# scrump.net
KiCad netlist of a schematic drawn in EAGLE
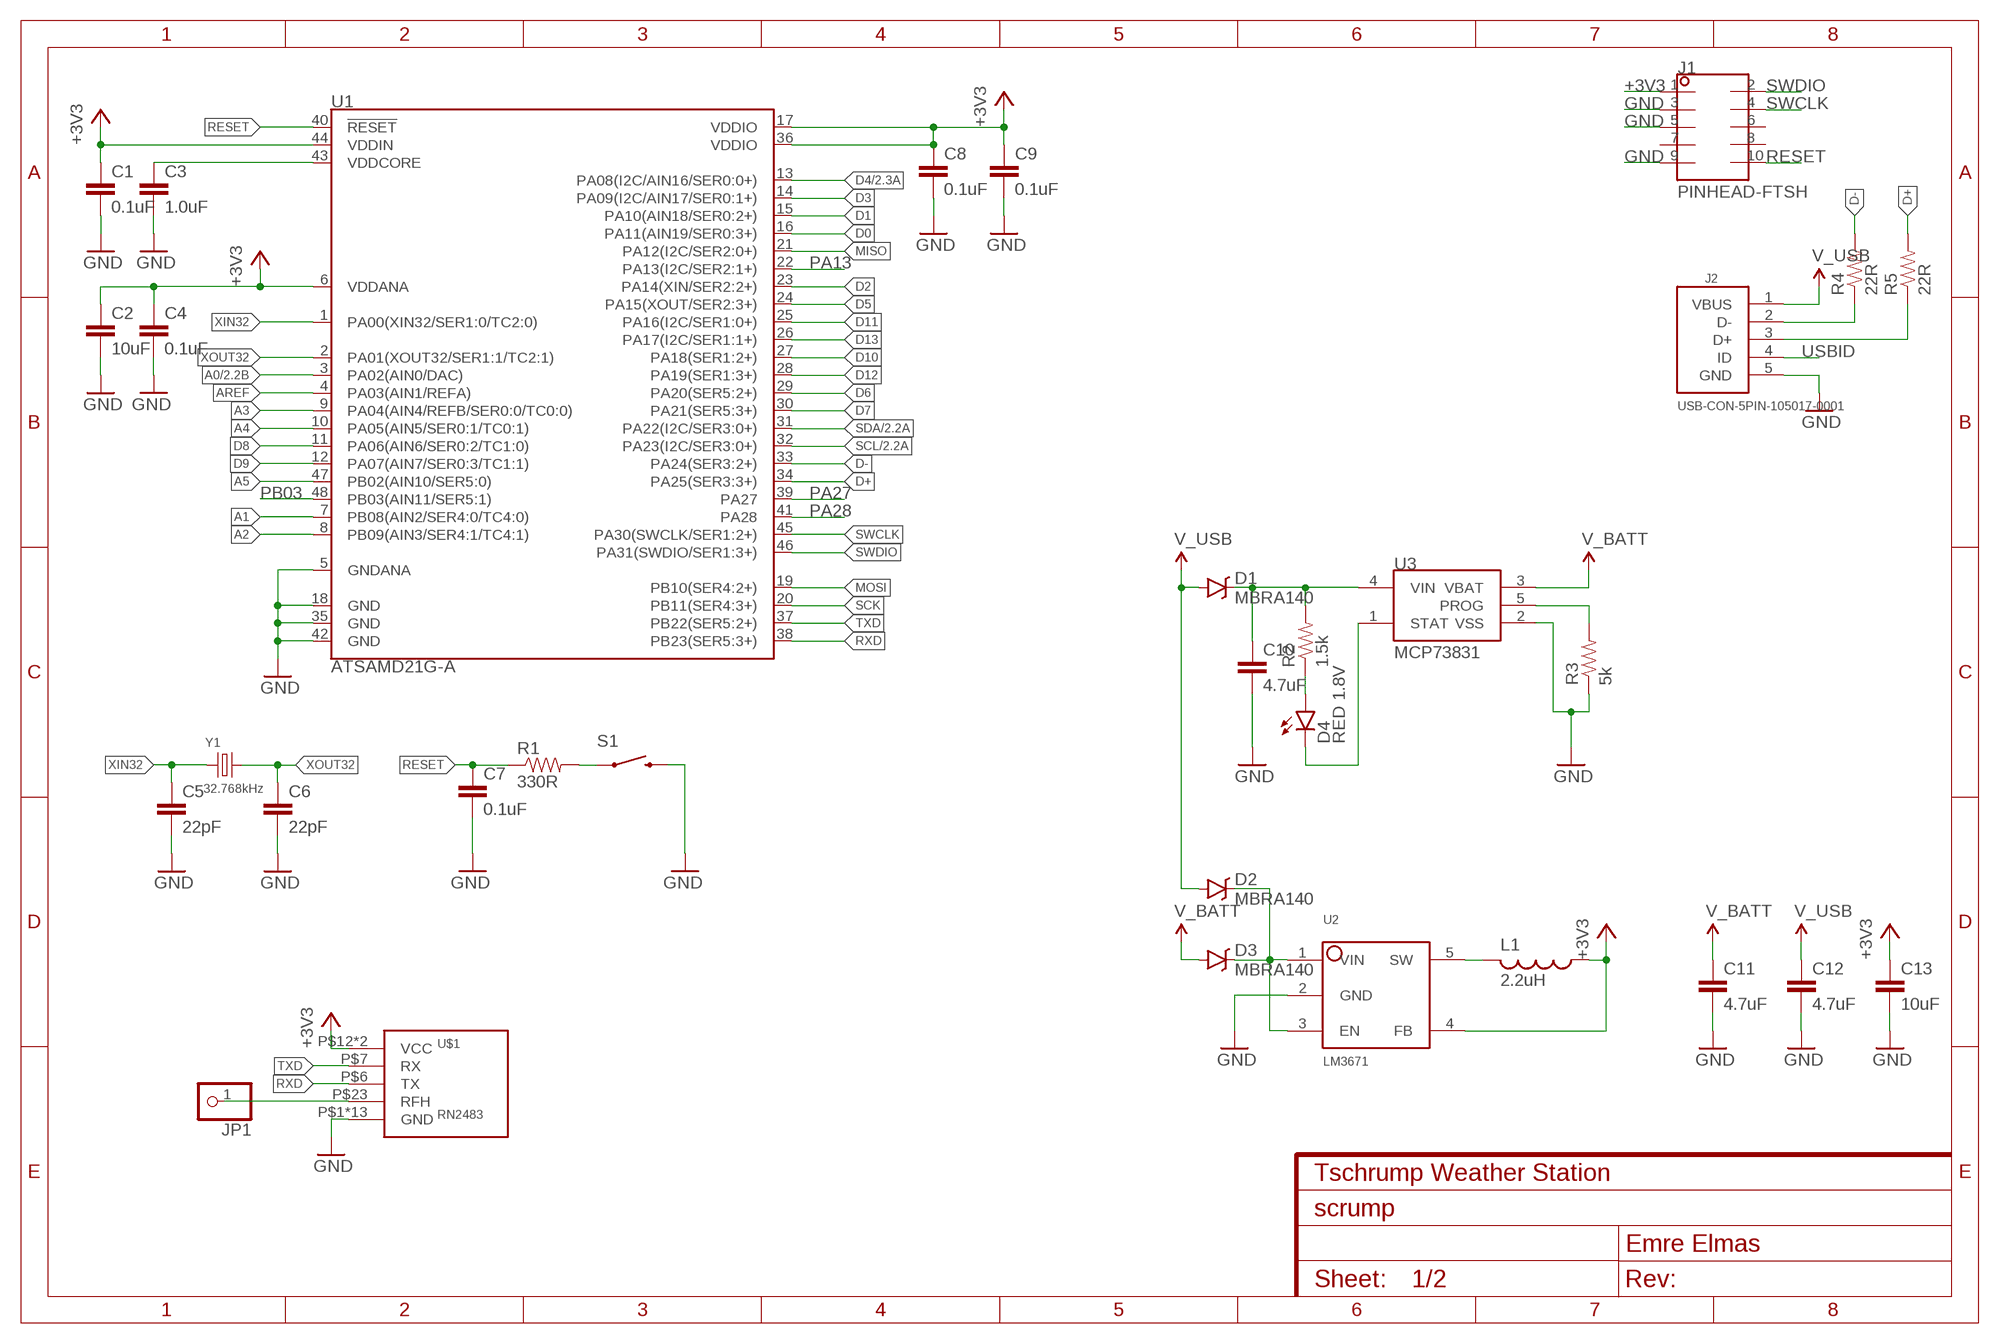
[diagram p0: schematic, sheet 1]
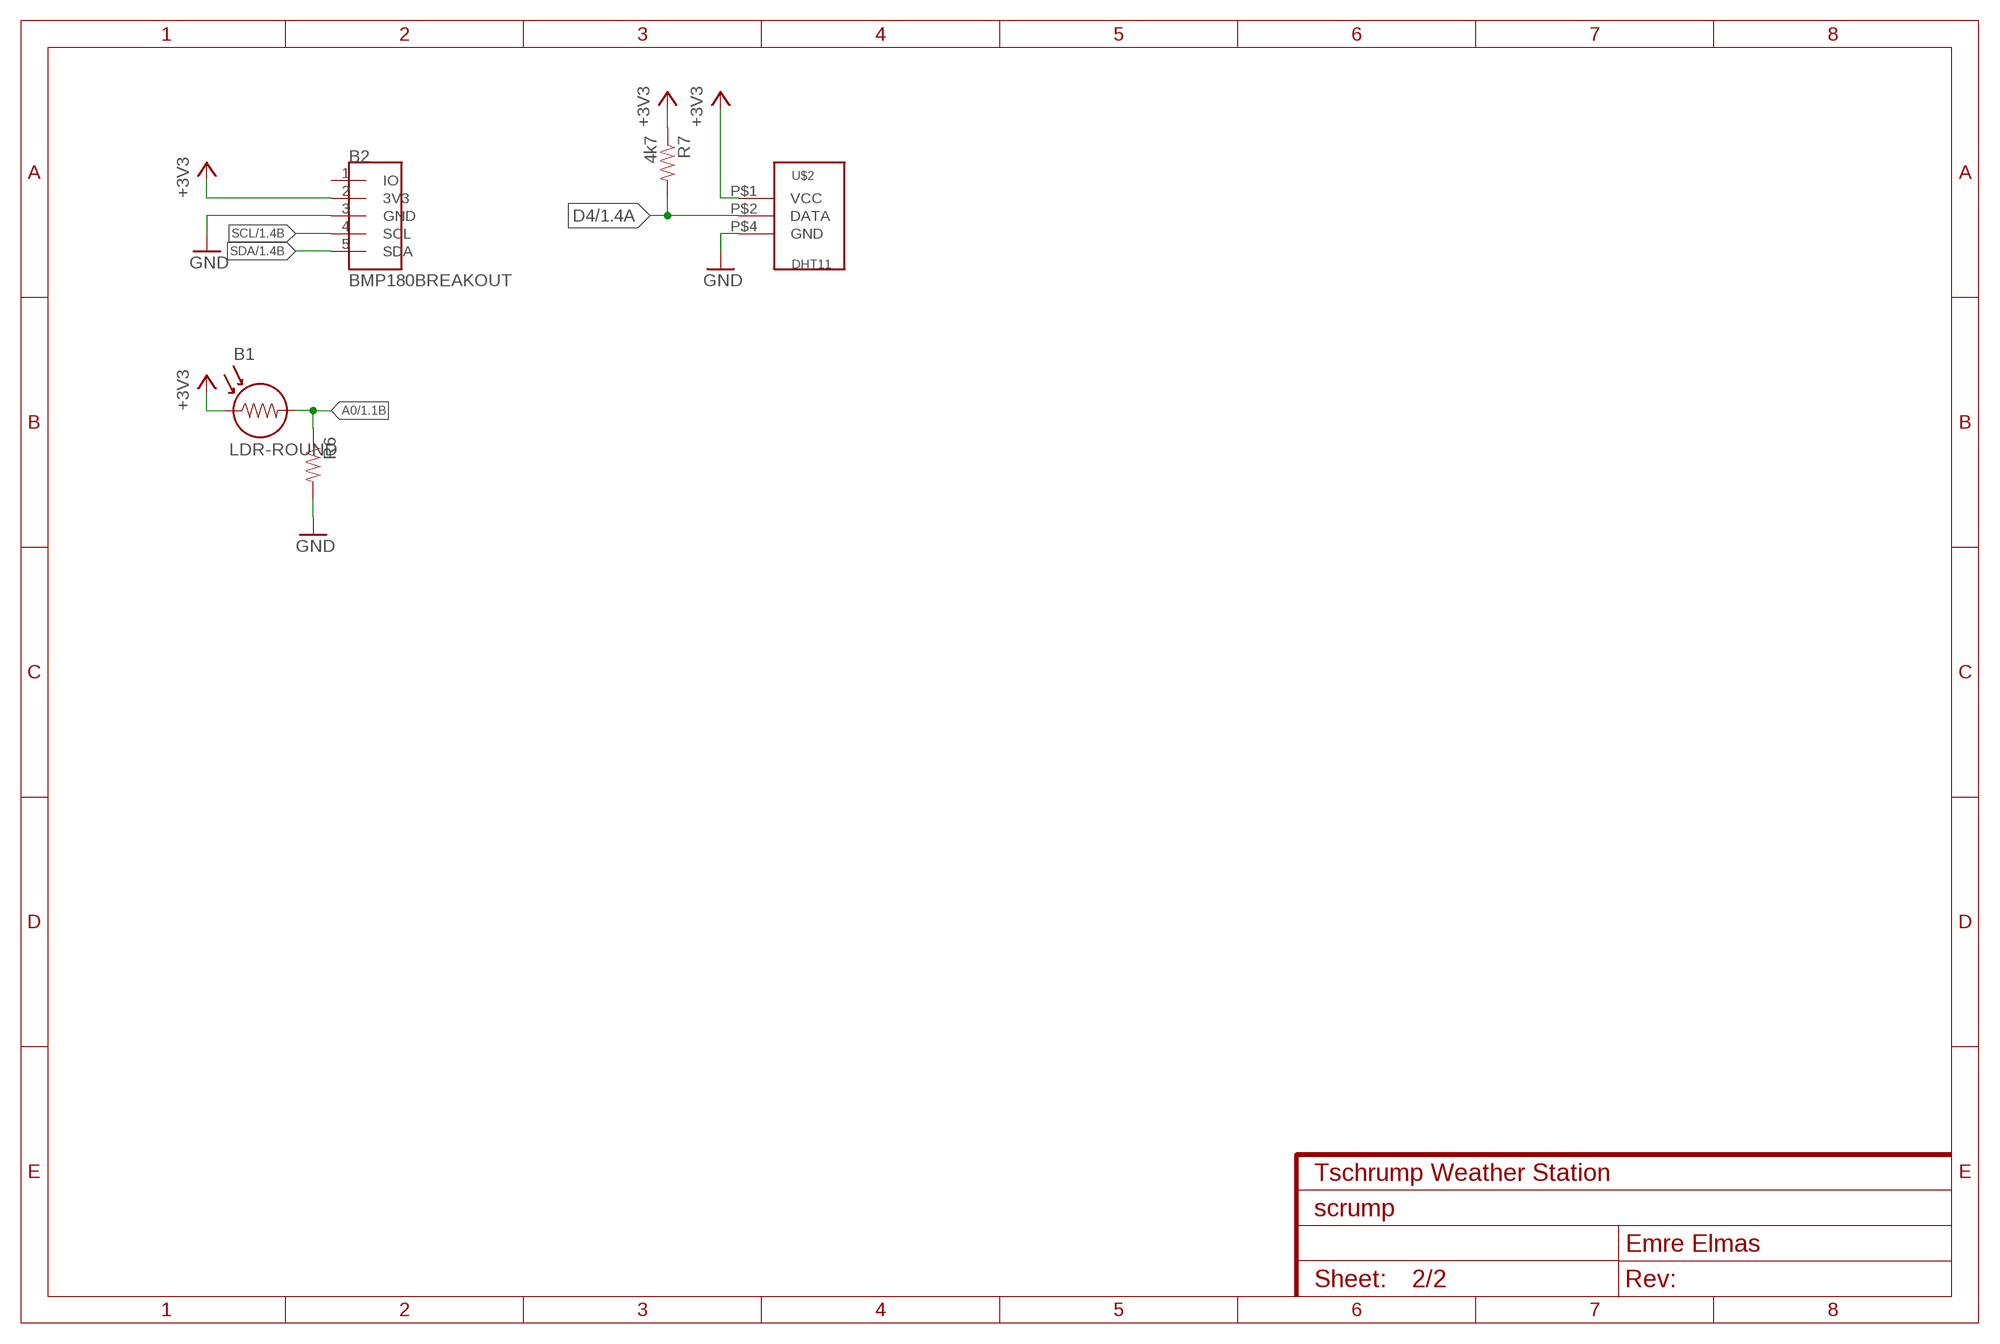
[diagram p1: schematic, sheet 2]

(export (version "E")
  (design (tool "Eeschema 10.0.6"))
  (components
    (comp (ref "B1")
      (value "LDR-ROUND")
      (footprint "eagle-import:LDR-ROUND")
      (libsource (lib "eagle-import") (part "LDR-ROUND"))
    )
    (comp (ref "B2")
      (value "BMP180BREAKOUT")
      (footprint "eagle-import:BMP180_BREAKOUT")
      (libsource (lib "eagle-import") (part "BMP180BREAKOUT"))
    )
    (comp (ref "R6")
      (value "RESISTOR0603")
      (footprint "eagle-import:0603-RES")
      (libsource (lib "eagle-import") (part "RESISTOR0603"))
    )
    (comp (ref "R7")
      (value "4k7")
      (footprint "eagle-import:0603-RES")
      (libsource (lib "eagle-import") (part "RESISTOR0603"))
    )
    (comp (ref "U$2")
      (value "DHT11")
      (footprint "eagle-import:DHT11")
      (libsource (lib "eagle-import") (part "DHT11"))
    )
    (comp (ref "C1")
      (value "0.1uF")
      (footprint "eagle-import:0603-CAP")
      (libsource (lib "eagle-import") (part "CAP0603-CAP"))
    )
    (comp (ref "C2")
      (value "10uF")
      (footprint "eagle-import:0603-CAP")
      (libsource (lib "eagle-import") (part "CAP0603-CAP"))
    )
    (comp (ref "C3")
      (value "1.0uF")
      (footprint "eagle-import:0603-CAP")
      (libsource (lib "eagle-import") (part "CAP0603-CAP"))
    )
    (comp (ref "C4")
      (value "0.1uF")
      (footprint "eagle-import:0603-CAP")
      (libsource (lib "eagle-import") (part "CAP0603-CAP"))
    )
    (comp (ref "C5")
      (value "22pF")
      (footprint "eagle-import:0603-CAP")
      (libsource (lib "eagle-import") (part "CAP0603-CAP"))
    )
    (comp (ref "C6")
      (value "22pF")
      (footprint "eagle-import:0603-CAP")
      (libsource (lib "eagle-import") (part "CAP0603-CAP"))
    )
    (comp (ref "C7")
      (value "0.1uF")
      (footprint "eagle-import:0603-CAP")
      (libsource (lib "eagle-import") (part "0.1UF-25V(+80/-20%)(0603)"))
    )
    (comp (ref "C8")
      (value "0.1uF")
      (footprint "eagle-import:0603-CAP")
      (libsource (lib "eagle-import") (part "CAP0603-CAP"))
    )
    (comp (ref "C9")
      (value "0.1uF")
      (footprint "eagle-import:0603-CAP")
      (libsource (lib "eagle-import") (part "CAP0603-CAP"))
    )
    (comp (ref "C10")
      (value "4.7uF")
      (footprint "eagle-import:0603-CAP")
      (libsource (lib "eagle-import") (part "CAP0603-CAP"))
    )
    (comp (ref "C11")
      (value "4.7uF")
      (footprint "eagle-import:0603-CAP")
      (libsource (lib "eagle-import") (part "CAP0603-CAP"))
    )
    (comp (ref "C12")
      (value "4.7uF")
      (footprint "eagle-import:0603-CAP")
      (libsource (lib "eagle-import") (part "CAP0603-CAP"))
    )
    (comp (ref "C13")
      (value "10uF")
      (footprint "eagle-import:0603-CAP")
      (libsource (lib "eagle-import") (part "CAP0603-CAP"))
    )
    (comp (ref "D1")
      (value "MBRA140")
      (footprint "eagle-import:SMA-DIODE")
      (libsource (lib "eagle-import") (part "MBRA140"))
    )
    (comp (ref "D2")
      (value "MBRA140")
      (footprint "eagle-import:SMA-DIODE")
      (libsource (lib "eagle-import") (part "MBRA140"))
    )
    (comp (ref "D3")
      (value "MBRA140")
      (footprint "eagle-import:SMA-DIODE")
      (libsource (lib "eagle-import") (part "MBRA140"))
    )
    (comp (ref "D4")
      (value "RED 1.8V")
      (footprint "eagle-import:LED-0603")
      (libsource (lib "eagle-import") (part "LED-RED0603"))
    )
    (comp (ref "J1")
      (value "PINHEAD-FTSH")
      (footprint "eagle-import:FTSH-105-01-XXX-DV-K")
      (libsource (lib "eagle-import") (part "PINHEAD-FTSH"))
    )
    (comp (ref "J2")
      (value "USB-CON-5PIN-105017-0001")
      (footprint "eagle-import:USB-MICRO-MOLEX-105017-0001")
      (libsource (lib "eagle-import") (part "USB-CON-5PIN-105017-0001"))
    )
    (comp (ref "JP1")
      (value "PINHD-1X1")
      (footprint "eagle-import:1X01")
      (libsource (lib "eagle-import") (part "PINHD-1X1"))
    )
    (comp (ref "L1")
      (value "2.2uH")
      (footprint "eagle-import:0806-INDUCTOR")
      (libsource (lib "eagle-import") (part "INDUCTOR"))
    )
    (comp (ref "R1")
      (value "330R")
      (footprint "eagle-import:0603-RES")
      (libsource (lib "eagle-import") (part "RESISTOR0603"))
    )
    (comp (ref "R2")
      (value "1.5k")
      (footprint "eagle-import:0603-RES")
      (libsource (lib "eagle-import") (part "RESISTOR0603"))
    )
    (comp (ref "R3")
      (value "5k")
      (footprint "eagle-import:0603-RES")
      (libsource (lib "eagle-import") (part "RESISTOR0603"))
    )
    (comp (ref "R4")
      (value "22R")
      (footprint "eagle-import:0603-RES")
      (libsource (lib "eagle-import") (part "RESISTOR0603"))
    )
    (comp (ref "R5")
      (value "22R")
      (footprint "eagle-import:0603-RES")
      (libsource (lib "eagle-import") (part "RESISTOR0603"))
    )
    (comp (ref "S1")
      (value "PUSHBUTTON-SMD")
      (footprint "eagle-import:TACTILE-SMD-SWITCH")
      (libsource (lib "eagle-import") (part "PUSHBUTTON-SMD"))
    )
    (comp (ref "U$1")
      (value "RN2483")
      (footprint "eagle-import:RN2483")
      (libsource (lib "eagle-import") (part "RN2483"))
    )
    (comp (ref "U1")
      (value "ATSAMD21G-A")
      (footprint "eagle-import:TQFP-48")
      (libsource (lib "eagle-import") (part "ATSAMD21G-A"))
    )
    (comp (ref "U2")
      (value "LM3671")
      (footprint "eagle-import:SOT23-5")
      (libsource (lib "eagle-import") (part "LM3671"))
    )
    (comp (ref "U3")
      (value "MCP73831")
      (footprint "eagle-import:SOT23-5")
      (libsource (lib "eagle-import") (part "MCP73831"))
    )
    (comp (ref "Y1")
      (value "32.768kHz")
      (footprint "eagle-import:ABS25")
      (libsource (lib "eagle-import") (part "CRYSTAL"))
    )
  )
  (nets
    (net (code "1") (name "+3V3") (class "Default")
      (node (ref "B1") (pin "P$1") (pinfunction "1_P$1") (pintype "passive"))
      (node (ref "B2") (pin "2") (pinfunction "3V3_2") (pintype "bidirectional"))
      (node (ref "C1") (pin "1") (pinfunction "1_1") (pintype "passive"))
      (node (ref "C13") (pin "1") (pinfunction "1_1") (pintype "passive"))
      (node (ref "C2") (pin "1") (pinfunction "1_1") (pintype "passive"))
      (node (ref "C4") (pin "1") (pinfunction "1_1") (pintype "passive"))
      (node (ref "C8") (pin "1") (pinfunction "1_1") (pintype "passive"))
      (node (ref "C9") (pin "1") (pinfunction "1_1") (pintype "passive"))
      (node (ref "J1") (pin "1") (pinfunction "P$1_1") (pintype "bidirectional"))
      (node (ref "L1") (pin "1") (pinfunction "1_1") (pintype "passive"))
      (node (ref "R7") (pin "1") (pinfunction "1_1") (pintype "passive"))
      (node (ref "U$1") (pin "P$12") (pinfunction "VCC_P$12") (pintype "bidirectional"))
      (node (ref "U$1") (pin "P$34") (pinfunction "VCC_P$34") (pintype "bidirectional"))
      (node (ref "U$2") (pin "P$1") (pinfunction "VCC_P$1") (pintype "bidirectional"))
      (node (ref "U1") (pin "17") (pinfunction "VDDIO_17") (pintype "bidirectional"))
      (node (ref "U1") (pin "36") (pinfunction "VDDIO_36") (pintype "bidirectional"))
      (node (ref "U1") (pin "44") (pinfunction "VDDIN_44") (pintype "bidirectional"))
      (node (ref "U1") (pin "6") (pinfunction "VDDANA_6") (pintype "bidirectional"))
      (node (ref "U2") (pin "4") (pinfunction "FB_4") (pintype "bidirectional"))
    )
    (net (code "2") (name "A0") (class "Default")
      (node (ref "B1") (pin "P$2") (pinfunction "2_P$2") (pintype "passive"))
      (node (ref "R6") (pin "1") (pinfunction "1_1") (pintype "passive"))
      (node (ref "U1") (pin "3") (pinfunction "PA02(AIN0/DAC)_3") (pintype "bidirectional"))
    )
    (net (code "3") (name "A1") (class "Default")
      (node (ref "U1") (pin "7") (pinfunction "PB08(AIN2/SER4:0/TC4:0)_7") (pintype "bidirectional"))
    )
    (net (code "4") (name "A2") (class "Default")
      (node (ref "U1") (pin "8") (pinfunction "PB09(AIN3/SER4:1/TC4:1)_8") (pintype "bidirectional"))
    )
    (net (code "5") (name "A3") (class "Default")
      (node (ref "U1") (pin "9") (pinfunction "PA04(AIN4/REFB/SER0:0/TC0:0)_9") (pintype "bidirectional"))
    )
    (net (code "6") (name "A4") (class "Default")
      (node (ref "U1") (pin "10") (pinfunction "PA05(AIN5/SER0:1/TC0:1)_10") (pintype "bidirectional"))
    )
    (net (code "7") (name "A5") (class "Default")
      (node (ref "U1") (pin "47") (pinfunction "PB02(AIN10/SER5:0)_47") (pintype "bidirectional"))
    )
    (net (code "8") (name "AREF") (class "Default")
      (node (ref "U1") (pin "4") (pinfunction "PA03(AIN1/REFA)_4") (pintype "bidirectional"))
    )
    (net (code "9") (name "D+") (class "Default")
      (node (ref "R5") (pin "2") (pinfunction "2_2") (pintype "passive"))
      (node (ref "U1") (pin "34") (pinfunction "PA25(SER3:3+)_34") (pintype "bidirectional"))
    )
    (net (code "10") (name "D-") (class "Default")
      (node (ref "R4") (pin "2") (pinfunction "2_2") (pintype "passive"))
      (node (ref "U1") (pin "33") (pinfunction "PA24(SER3:2+)_33") (pintype "bidirectional"))
    )
    (net (code "11") (name "D0") (class "Default")
      (node (ref "U1") (pin "16") (pinfunction "PA11(AIN19/SER0:3+)_16") (pintype "bidirectional"))
    )
    (net (code "12") (name "D1") (class "Default")
      (node (ref "U1") (pin "15") (pinfunction "PA10(AIN18/SER0:2+)_15") (pintype "bidirectional"))
    )
    (net (code "13") (name "D2") (class "Default")
      (node (ref "U1") (pin "23") (pinfunction "PA14(XIN/SER2:2+)_23") (pintype "bidirectional"))
    )
    (net (code "14") (name "D3") (class "Default")
      (node (ref "U1") (pin "14") (pinfunction "PA09(I2C/AIN17/SER0:1+)_14") (pintype "bidirectional"))
    )
    (net (code "15") (name "D4") (class "Default")
      (node (ref "R7") (pin "2") (pinfunction "2_2") (pintype "passive"))
      (node (ref "U$2") (pin "P$2") (pinfunction "DATA_P$2") (pintype "bidirectional"))
      (node (ref "U1") (pin "13") (pinfunction "PA08(I2C/AIN16/SER0:0+)_13") (pintype "bidirectional"))
    )
    (net (code "16") (name "D5") (class "Default")
      (node (ref "U1") (pin "24") (pinfunction "PA15(XOUT/SER2:3+)_24") (pintype "bidirectional"))
    )
    (net (code "17") (name "D6") (class "Default")
      (node (ref "U1") (pin "29") (pinfunction "PA20(SER5:2+)_29") (pintype "bidirectional"))
    )
    (net (code "18") (name "D7") (class "Default")
      (node (ref "U1") (pin "30") (pinfunction "PA21(SER5:3+)_30") (pintype "bidirectional"))
    )
    (net (code "19") (name "D8") (class "Default")
      (node (ref "U1") (pin "11") (pinfunction "PA06(AIN6/SER0:2/TC1:0)_11") (pintype "bidirectional"))
    )
    (net (code "20") (name "D9") (class "Default")
      (node (ref "U1") (pin "12") (pinfunction "PA07(AIN7/SER0:3/TC1:1)_12") (pintype "bidirectional"))
    )
    (net (code "21") (name "D10") (class "Default")
      (node (ref "U1") (pin "27") (pinfunction "PA18(SER1:2+)_27") (pintype "bidirectional"))
    )
    (net (code "22") (name "D11") (class "Default")
      (node (ref "U1") (pin "25") (pinfunction "PA16(I2C/SER1:0+)_25") (pintype "bidirectional"))
    )
    (net (code "23") (name "D12") (class "Default")
      (node (ref "U1") (pin "28") (pinfunction "PA19(SER1:3+)_28") (pintype "bidirectional"))
    )
    (net (code "24") (name "D13") (class "Default")
      (node (ref "U1") (pin "26") (pinfunction "PA17(I2C/SER1:1+)_26") (pintype "bidirectional"))
    )
    (net (code "25") (name "GND") (class "Default")
      (node (ref "B2") (pin "3") (pinfunction "GND_3") (pintype "bidirectional"))
      (node (ref "C1") (pin "2") (pinfunction "2_2") (pintype "passive"))
      (node (ref "C10") (pin "2") (pinfunction "2_2") (pintype "passive"))
      (node (ref "C11") (pin "2") (pinfunction "2_2") (pintype "passive"))
      (node (ref "C12") (pin "2") (pinfunction "2_2") (pintype "passive"))
      (node (ref "C13") (pin "2") (pinfunction "2_2") (pintype "passive"))
      (node (ref "C2") (pin "2") (pinfunction "2_2") (pintype "passive"))
      (node (ref "C3") (pin "2") (pinfunction "2_2") (pintype "passive"))
      (node (ref "C4") (pin "2") (pinfunction "2_2") (pintype "passive"))
      (node (ref "C5") (pin "2") (pinfunction "2_2") (pintype "passive"))
      (node (ref "C6") (pin "2") (pinfunction "2_2") (pintype "passive"))
      (node (ref "C7") (pin "2") (pinfunction "2_2") (pintype "passive"))
      (node (ref "C8") (pin "2") (pinfunction "2_2") (pintype "passive"))
      (node (ref "C9") (pin "2") (pinfunction "2_2") (pintype "passive"))
      (node (ref "J1") (pin "3") (pinfunction "P$3_3") (pintype "bidirectional"))
      (node (ref "J1") (pin "5") (pinfunction "P$5_5") (pintype "bidirectional"))
      (node (ref "J1") (pin "9") (pinfunction "P$9_9") (pintype "bidirectional"))
      (node (ref "J2") (pin "5") (pinfunction "GND_5") (pintype "power_in"))
      (node (ref "R3") (pin "1") (pinfunction "1_1") (pintype "passive"))
      (node (ref "R6") (pin "2") (pinfunction "2_2") (pintype "passive"))
      (node (ref "S1") (pin "P$3") (pinfunction "2_P$3") (pintype "passive"))
      (node (ref "S1") (pin "P$4") (pinfunction "2_P$4") (pintype "passive"))
      (node (ref "U$1") (pin "P$1") (pinfunction "GND_P$1") (pintype "bidirectional"))
      (node (ref "U$1") (pin "P$11") (pinfunction "GND_P$11") (pintype "bidirectional"))
      (node (ref "U$1") (pin "P$20") (pinfunction "GND_P$20") (pintype "bidirectional"))
      (node (ref "U$1") (pin "P$21") (pinfunction "GND_P$21") (pintype "bidirectional"))
      (node (ref "U$1") (pin "P$22") (pinfunction "GND_P$22") (pintype "bidirectional"))
      (node (ref "U$1") (pin "P$24") (pinfunction "GND_P$24") (pintype "bidirectional"))
      (node (ref "U$1") (pin "P$26") (pinfunction "GND_P$26") (pintype "bidirectional"))
      (node (ref "U$1") (pin "P$27") (pinfunction "GND_P$27") (pintype "bidirectional"))
      (node (ref "U$1") (pin "P$28") (pinfunction "GND_P$28") (pintype "bidirectional"))
      (node (ref "U$1") (pin "P$33") (pinfunction "GND_P$33") (pintype "bidirectional"))
      (node (ref "U$1") (pin "P$41") (pinfunction "GND_P$41") (pintype "bidirectional"))
      (node (ref "U$1") (pin "P$47") (pinfunction "GND_P$47") (pintype "bidirectional"))
      (node (ref "U$1") (pin "P$8") (pinfunction "GND_P$8") (pintype "bidirectional"))
      (node (ref "U$2") (pin "P$4") (pinfunction "GND_P$4") (pintype "bidirectional"))
      (node (ref "U1") (pin "18") (pinfunction "GND_18") (pintype "bidirectional"))
      (node (ref "U1") (pin "35") (pinfunction "GND_35") (pintype "bidirectional"))
      (node (ref "U1") (pin "42") (pinfunction "GND_42") (pintype "bidirectional"))
      (node (ref "U1") (pin "5") (pinfunction "GNDANA_5") (pintype "bidirectional"))
      (node (ref "U2") (pin "2") (pinfunction "GND_2") (pintype "bidirectional"))
      (node (ref "U3") (pin "2") (pinfunction "VSS_2") (pintype "bidirectional"))
    )
    (net (code "26") (name "MISO") (class "Default")
      (node (ref "U1") (pin "21") (pinfunction "PA12(I2C/SER2:0+)_21") (pintype "bidirectional"))
    )
    (net (code "27") (name "MOSI") (class "Default")
      (node (ref "U1") (pin "19") (pinfunction "PB10(SER4:2+)_19") (pintype "bidirectional"))
    )
    (net (code "28") (name "Net-(D4-PadA)") (class "Default")
      (node (ref "D4") (pin "A") (pinfunction "A_A") (pintype "passive"))
      (node (ref "R2") (pin "1") (pinfunction "1_1") (pintype "passive"))
    )
    (net (code "29") (name "Net-(J2-D+)") (class "Default")
      (node (ref "J2") (pin "3") (pinfunction "D+_3") (pintype "bidirectional"))
      (node (ref "R5") (pin "1") (pinfunction "1_1") (pintype "passive"))
    )
    (net (code "30") (name "Net-(J2-D-)") (class "Default")
      (node (ref "J2") (pin "2") (pinfunction "D-_2") (pintype "bidirectional"))
      (node (ref "R4") (pin "1") (pinfunction "1_1") (pintype "passive"))
    )
    (net (code "31") (name "Net-(R1-Pad2)") (class "Default")
      (node (ref "R1") (pin "2") (pinfunction "2_2") (pintype "passive"))
      (node (ref "S1") (pin "P$1") (pinfunction "1_P$1") (pintype "passive"))
      (node (ref "S1") (pin "P$2") (pinfunction "1_P$2") (pintype "passive"))
    )
    (net (code "32") (name "Net-(U$1-RFH)") (class "Default")
      (node (ref "JP1") (pin "1") (pinfunction "1_1") (pintype "passive"))
      (node (ref "U$1") (pin "P$23") (pinfunction "RFH_P$23") (pintype "bidirectional"))
    )
    (net (code "33") (name "Net-(U1-VDDCORE)") (class "Default")
      (node (ref "C3") (pin "1") (pinfunction "1_1") (pintype "passive"))
      (node (ref "U1") (pin "43") (pinfunction "VDDCORE_43") (pintype "bidirectional"))
    )
    (net (code "34") (name "Net-(U2-EN)") (class "Default")
      (node (ref "D2") (pin "C") (pinfunction "C_C") (pintype "passive"))
      (node (ref "D3") (pin "C") (pinfunction "C_C") (pintype "passive"))
      (node (ref "U2") (pin "1") (pinfunction "VIN_1") (pintype "bidirectional"))
      (node (ref "U2") (pin "3") (pinfunction "EN_3") (pintype "bidirectional"))
    )
    (net (code "35") (name "Net-(U2-SW)") (class "Default")
      (node (ref "L1") (pin "2") (pinfunction "2_2") (pintype "passive"))
      (node (ref "U2") (pin "5") (pinfunction "SW_5") (pintype "bidirectional"))
    )
    (net (code "36") (name "Net-(U3-PROG)") (class "Default")
      (node (ref "R3") (pin "2") (pinfunction "2_2") (pintype "passive"))
      (node (ref "U3") (pin "5") (pinfunction "PROG_5") (pintype "bidirectional"))
    )
    (net (code "37") (name "Net-(U3-STAT)") (class "Default")
      (node (ref "D4") (pin "C") (pinfunction "C_C") (pintype "passive"))
      (node (ref "U3") (pin "1") (pinfunction "STAT_1") (pintype "bidirectional"))
    )
    (net (code "38") (name "Net-(U3-VIN)") (class "Default")
      (node (ref "C10") (pin "1") (pinfunction "1_1") (pintype "passive"))
      (node (ref "D1") (pin "C") (pinfunction "C_C") (pintype "passive"))
      (node (ref "R2") (pin "2") (pinfunction "2_2") (pintype "passive"))
      (node (ref "U3") (pin "4") (pinfunction "VIN_4") (pintype "bidirectional"))
    )
    (net (code "39") (name "PA13") (class "Default")
      (node (ref "U1") (pin "22") (pinfunction "PA13(I2C/SER2:1+)_22") (pintype "bidirectional"))
    )
    (net (code "40") (name "PA27") (class "Default")
      (node (ref "U1") (pin "39") (pinfunction "PA27_39") (pintype "bidirectional"))
    )
    (net (code "41") (name "PA28") (class "Default")
      (node (ref "U1") (pin "41") (pinfunction "PA28_41") (pintype "bidirectional"))
    )
    (net (code "42") (name "PB03") (class "Default")
      (node (ref "U1") (pin "48") (pinfunction "PB03(AIN11/SER5:1)_48") (pintype "bidirectional"))
    )
    (net (code "43") (name "RESET") (class "Default")
      (node (ref "C7") (pin "1") (pinfunction "1_1") (pintype "passive"))
      (node (ref "J1") (pin "10") (pinfunction "P$10_10") (pintype "bidirectional"))
      (node (ref "R1") (pin "1") (pinfunction "1_1") (pintype "passive"))
      (node (ref "U1") (pin "40") (pinfunction "~{RESET}_40") (pintype "bidirectional"))
    )
    (net (code "44") (name "RXD") (class "Default")
      (node (ref "U$1") (pin "P$6") (pinfunction "TX_P$6") (pintype "bidirectional"))
      (node (ref "U1") (pin "38") (pinfunction "PB23(SER5:3+)_38") (pintype "bidirectional"))
    )
    (net (code "45") (name "SCK") (class "Default")
      (node (ref "U1") (pin "20") (pinfunction "PB11(SER4:3+)_20") (pintype "bidirectional"))
    )
    (net (code "46") (name "SCL") (class "Default")
      (node (ref "B2") (pin "4") (pinfunction "SCL_4") (pintype "bidirectional"))
      (node (ref "U1") (pin "32") (pinfunction "PA23(I2C/SER3:0+)_32") (pintype "bidirectional"))
    )
    (net (code "47") (name "SDA") (class "Default")
      (node (ref "B2") (pin "5") (pinfunction "SDA_5") (pintype "bidirectional"))
      (node (ref "U1") (pin "31") (pinfunction "PA22(I2C/SER3:0+)_31") (pintype "bidirectional"))
    )
    (net (code "48") (name "SWCLK") (class "Default")
      (node (ref "J1") (pin "4") (pinfunction "P$4_4") (pintype "bidirectional"))
      (node (ref "U1") (pin "45") (pinfunction "PA30(SWCLK/SER1:2+)_45") (pintype "bidirectional"))
    )
    (net (code "49") (name "SWDIO") (class "Default")
      (node (ref "J1") (pin "2") (pinfunction "P$2_2") (pintype "bidirectional"))
      (node (ref "U1") (pin "46") (pinfunction "PA31(SWDIO/SER1:3+)_46") (pintype "bidirectional"))
    )
    (net (code "50") (name "TXD") (class "Default")
      (node (ref "U$1") (pin "P$7") (pinfunction "RX_P$7") (pintype "bidirectional"))
      (node (ref "U1") (pin "37") (pinfunction "PB22(SER5:2+)_37") (pintype "bidirectional"))
    )
    (net (code "51") (name "USBID") (class "Default")
      (node (ref "J2") (pin "4") (pinfunction "ID_4") (pintype "bidirectional"))
    )
    (net (code "52") (name "V_BATT") (class "Default")
      (node (ref "C11") (pin "1") (pinfunction "1_1") (pintype "passive"))
      (node (ref "D3") (pin "A") (pinfunction "A_A") (pintype "passive"))
      (node (ref "U3") (pin "3") (pinfunction "VBAT_3") (pintype "bidirectional"))
    )
    (net (code "53") (name "V_USB") (class "Default")
      (node (ref "C12") (pin "1") (pinfunction "1_1") (pintype "passive"))
      (node (ref "D1") (pin "A") (pinfunction "A_A") (pintype "passive"))
      (node (ref "D2") (pin "A") (pinfunction "A_A") (pintype "passive"))
      (node (ref "J2") (pin "1") (pinfunction "VBUS_1") (pintype "power_in"))
    )
    (net (code "54") (name "XIN32") (class "Default")
      (node (ref "C5") (pin "1") (pinfunction "1_1") (pintype "passive"))
      (node (ref "U1") (pin "1") (pinfunction "PA00(XIN32/SER1:0/TC2:0)_1") (pintype "bidirectional"))
      (node (ref "Y1") (pin "P$1") (pinfunction "1_P$1") (pintype "passive"))
    )
    (net (code "55") (name "XOUT32") (class "Default")
      (node (ref "C6") (pin "1") (pinfunction "1_1") (pintype "passive"))
      (node (ref "U1") (pin "2") (pinfunction "PA01(XOUT32/SER1:1/TC2:1)_2") (pintype "bidirectional"))
      (node (ref "Y1") (pin "P$4") (pinfunction "3_P$4") (pintype "passive"))
    )
    (net (code "56") (name "unconnected-(B2-IO-Pad1)") (class "Default")
      (node (ref "B2") (pin "1") (pinfunction "IO_1") (pintype "bidirectional"))
    )
    (net (code "57") (name "unconnected-(J1-P$6-Pad6)") (class "Default")
      (node (ref "J1") (pin "6") (pinfunction "P$6_6") (pintype "bidirectional"))
    )
    (net (code "58") (name "unconnected-(J1-P$7-Pad7)") (class "Default")
      (node (ref "J1") (pin "7") (pinfunction "P$7_7") (pintype "bidirectional"))
    )
    (net (code "59") (name "unconnected-(J1-P$8-Pad8)") (class "Default")
      (node (ref "J1") (pin "8") (pinfunction "P$8_8") (pintype "bidirectional"))
    )
  )
)
